# triax-arm-quad-mmcx-passthrough.net
KiCad netlist of a schematic drawn in EAGLE
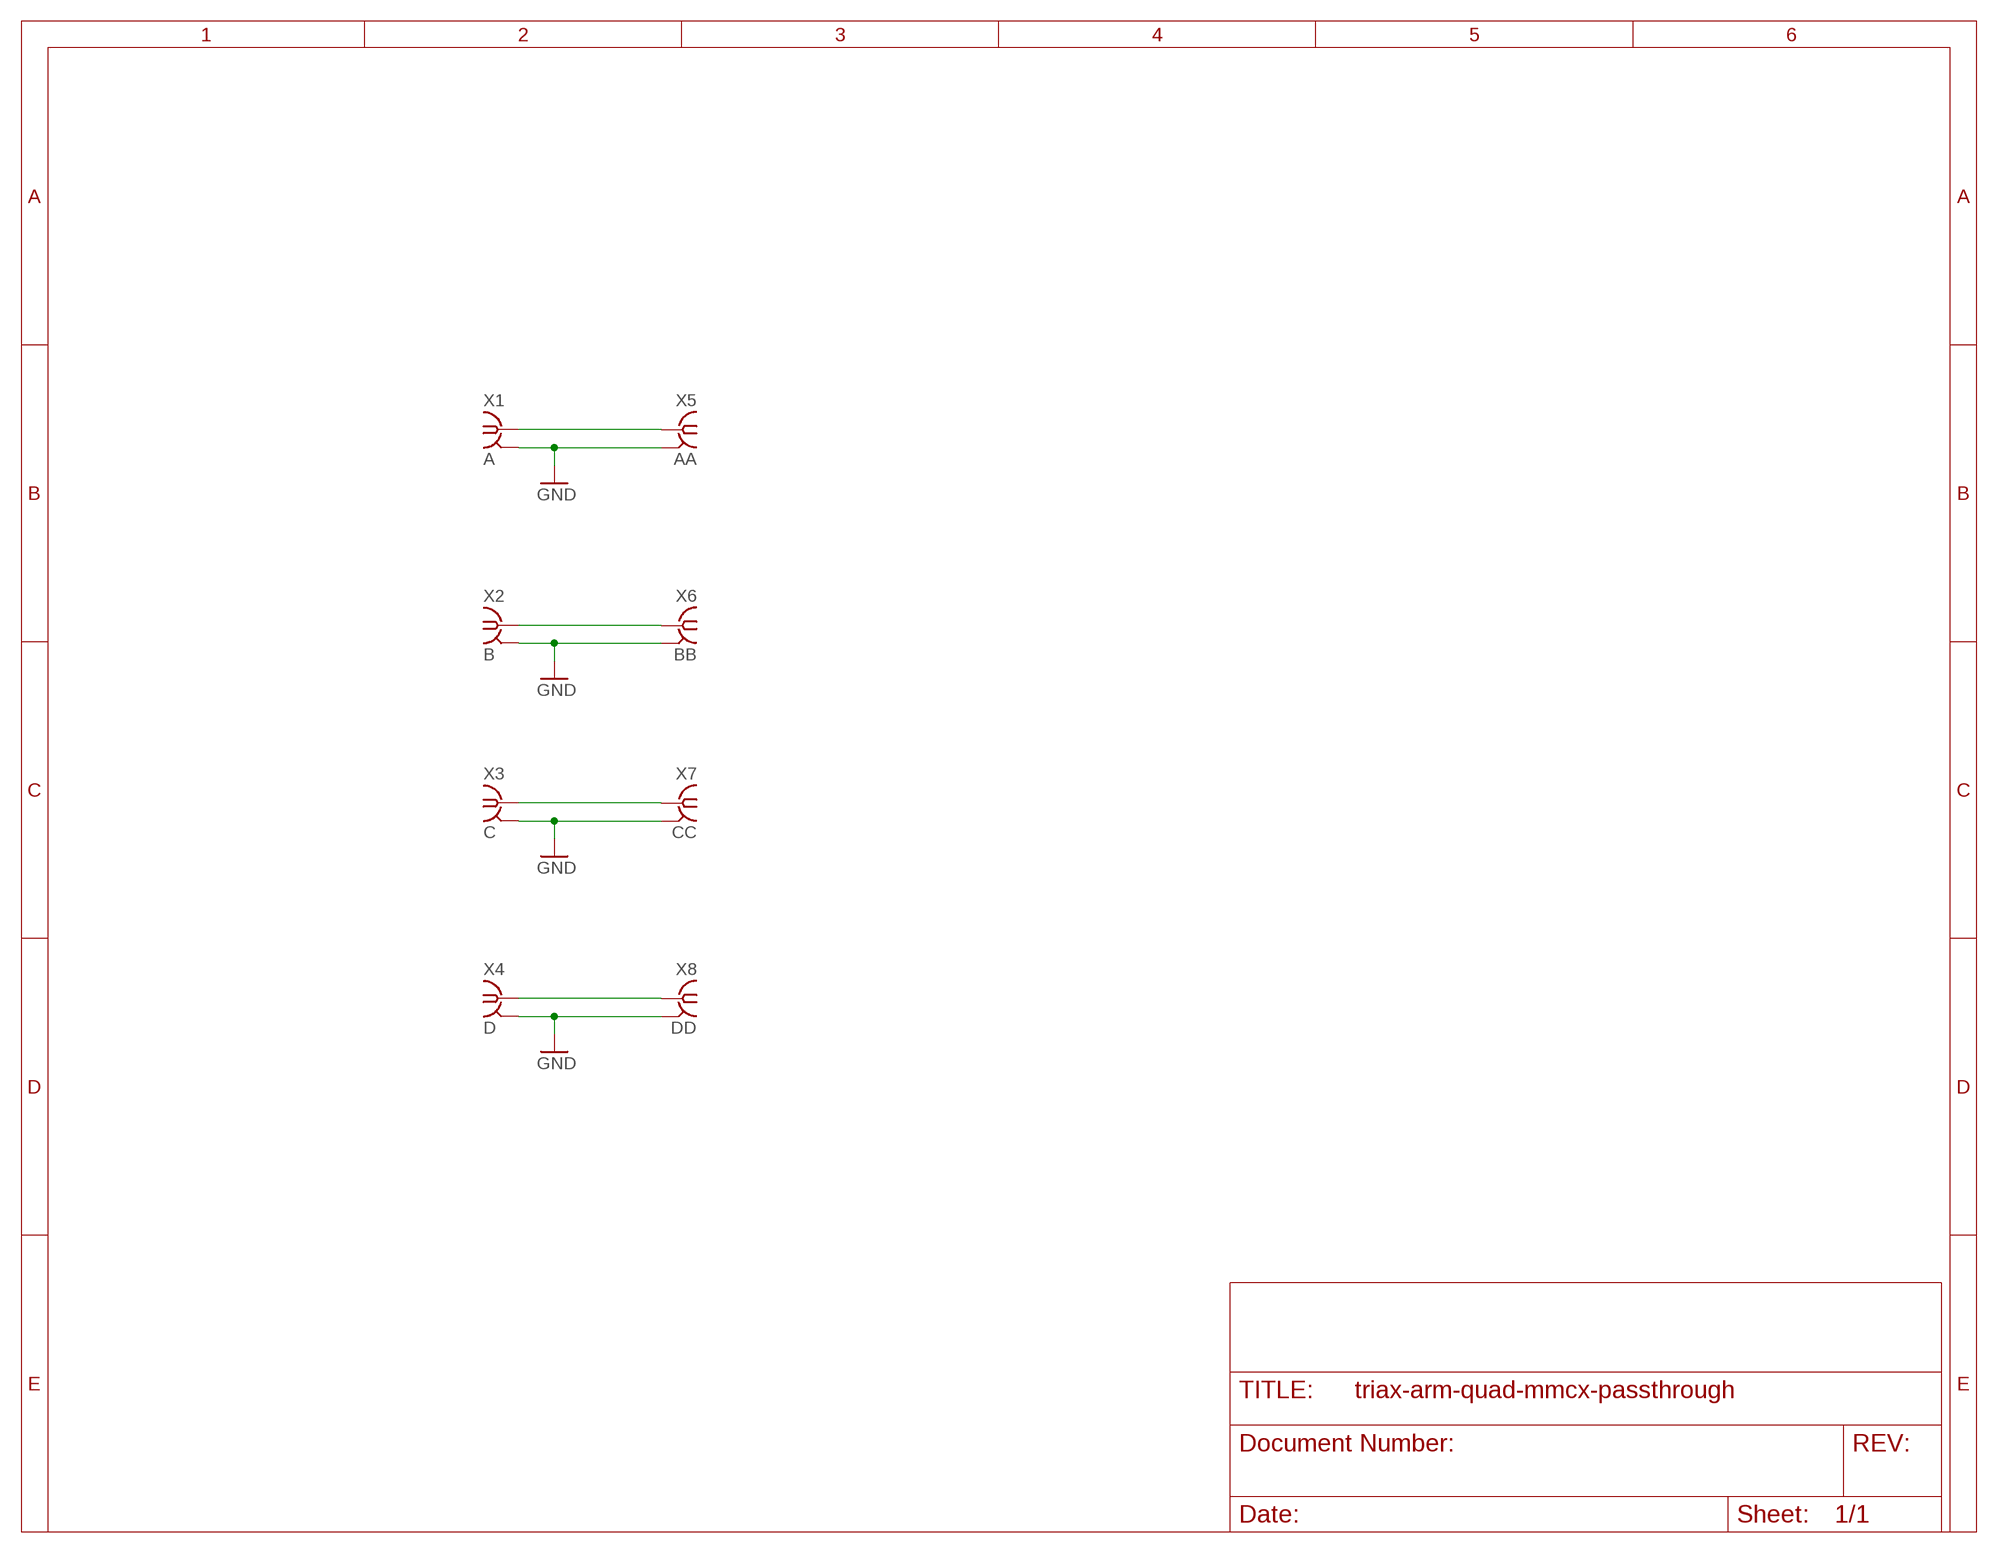
[diagram p0: schematic, sheet 1]

(export (version "E")
  (design (tool "Eeschema 10.0.6"))
  (components
    (comp (ref "X1")
      (value "A")
      (footprint "eagle-import:MMCX-J-P-X-ST-EM1-MKT")
      (libsource (lib "eagle-import") (part "COAX"))
    )
    (comp (ref "X2")
      (value "B")
      (footprint "eagle-import:MMCX-J-P-X-ST-EM1-MKT")
      (libsource (lib "eagle-import") (part "COAX"))
    )
    (comp (ref "X3")
      (value "C")
      (footprint "eagle-import:MMCX-J-P-X-ST-EM1-MKT")
      (libsource (lib "eagle-import") (part "COAX"))
    )
    (comp (ref "X4")
      (value "D")
      (footprint "eagle-import:MMCX-J-P-X-ST-EM1-MKT")
      (libsource (lib "eagle-import") (part "COAX"))
    )
    (comp (ref "X5")
      (value "AA")
      (footprint "eagle-import:MMCX-J-P-X-ST-EM1-MKT")
      (libsource (lib "eagle-import") (part "COAX"))
    )
    (comp (ref "X6")
      (value "BB")
      (footprint "eagle-import:MMCX-J-P-X-ST-EM1-MKT")
      (libsource (lib "eagle-import") (part "COAX"))
    )
    (comp (ref "X7")
      (value "CC")
      (footprint "eagle-import:MMCX-J-P-X-ST-EM1-MKT")
      (libsource (lib "eagle-import") (part "COAX"))
    )
    (comp (ref "X8")
      (value "DD")
      (footprint "eagle-import:MMCX-J-P-X-ST-EM1-MKT")
      (libsource (lib "eagle-import") (part "COAX"))
    )
  )
  (nets
    (net (code "1") (name "GND") (class "Default")
      (node (ref "X1") (pin "2@1") (pinfunction "GND_2@1") (pintype "power_in"))
      (node (ref "X2") (pin "2@1") (pinfunction "GND_2@1") (pintype "power_in"))
      (node (ref "X3") (pin "2@1") (pinfunction "GND_2@1") (pintype "power_in"))
      (node (ref "X4") (pin "2@1") (pinfunction "GND_2@1") (pintype "power_in"))
      (node (ref "X5") (pin "2@1") (pinfunction "GND_2@1") (pintype "power_in"))
      (node (ref "X6") (pin "2@1") (pinfunction "GND_2@1") (pintype "power_in"))
      (node (ref "X7") (pin "2@1") (pinfunction "GND_2@1") (pintype "power_in"))
      (node (ref "X8") (pin "2@1") (pinfunction "GND_2@1") (pintype "power_in"))
    )
    (net (code "2") (name "Net-(X1-Pad1)") (class "Default")
      (node (ref "X1") (pin "1") (pinfunction "1_1") (pintype "passive"))
      (node (ref "X5") (pin "1") (pinfunction "1_1") (pintype "passive"))
    )
    (net (code "3") (name "Net-(X2-Pad1)") (class "Default")
      (node (ref "X2") (pin "1") (pinfunction "1_1") (pintype "passive"))
      (node (ref "X6") (pin "1") (pinfunction "1_1") (pintype "passive"))
    )
    (net (code "4") (name "Net-(X3-Pad1)") (class "Default")
      (node (ref "X3") (pin "1") (pinfunction "1_1") (pintype "passive"))
      (node (ref "X7") (pin "1") (pinfunction "1_1") (pintype "passive"))
    )
    (net (code "5") (name "Net-(X4-Pad1)") (class "Default")
      (node (ref "X4") (pin "1") (pinfunction "1_1") (pintype "passive"))
      (node (ref "X8") (pin "1") (pinfunction "1_1") (pintype "passive"))
    )
  )
)
